# DC-DC-Converters_3.net
KiCad netlist of a schematic drawn in Altium Designer
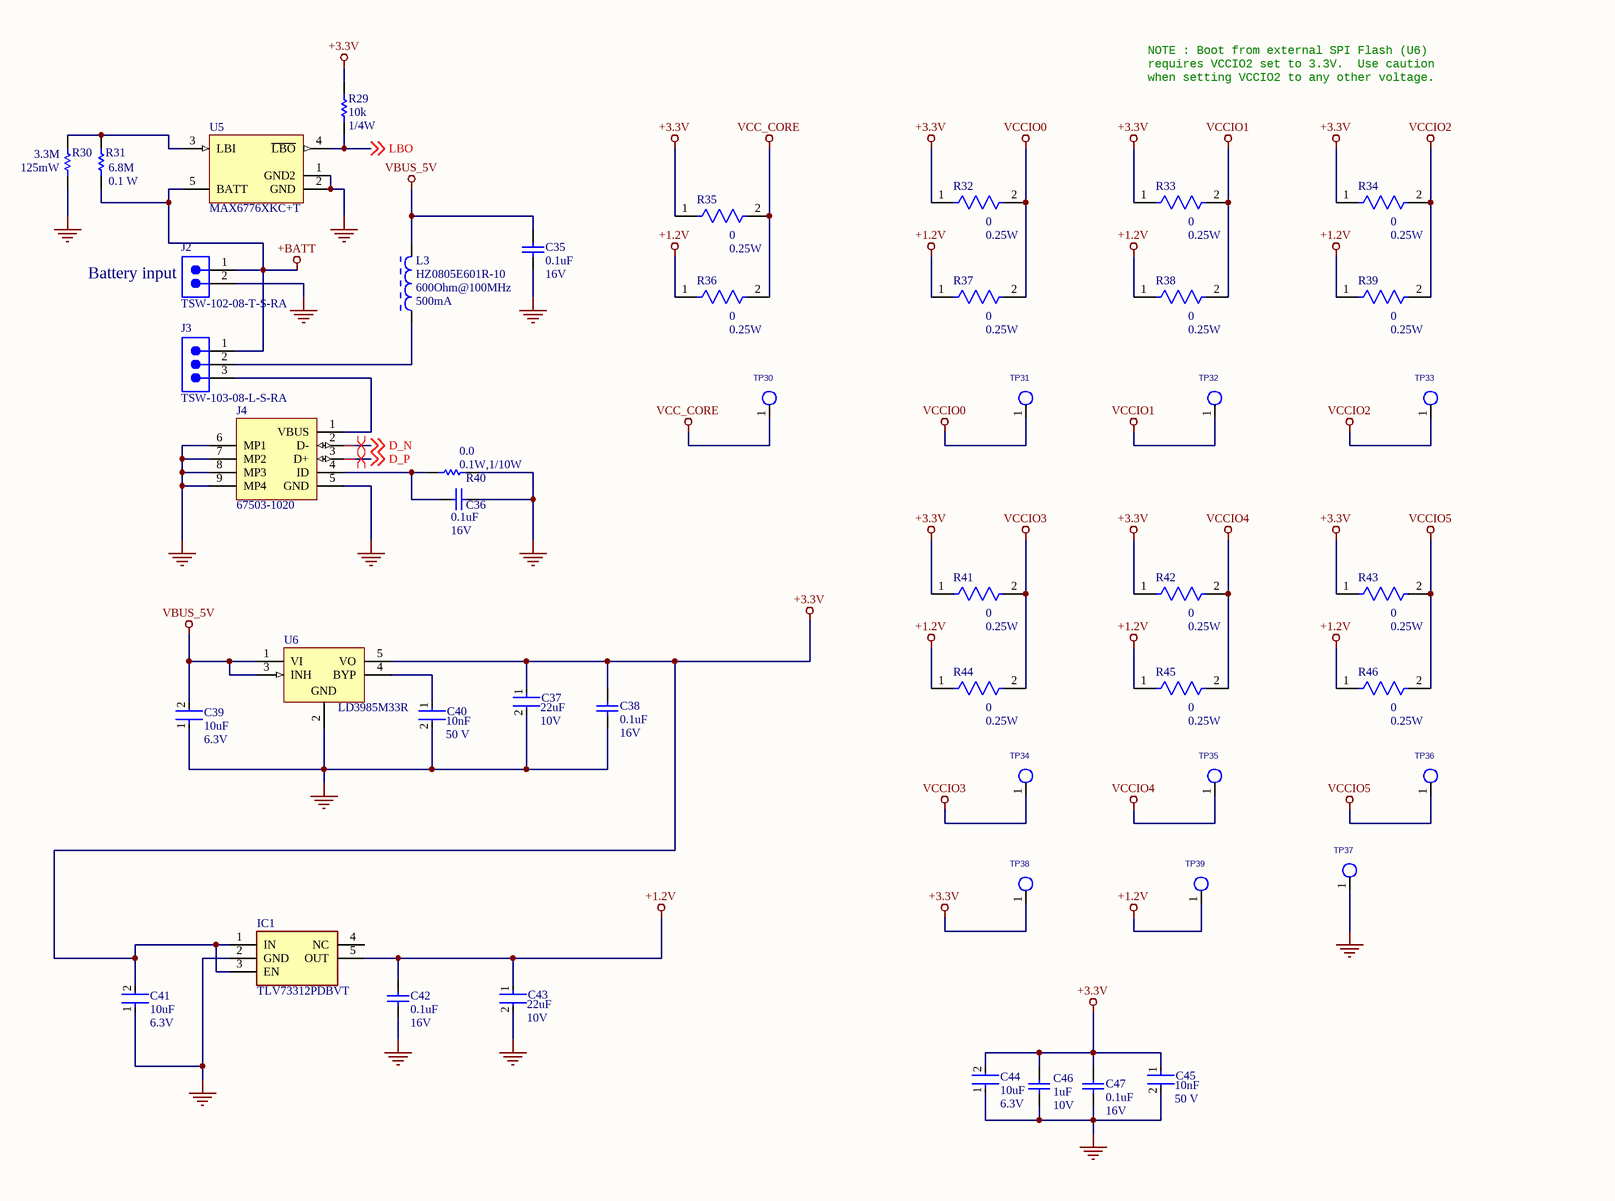
[diagram p0: DC-DC-Converters 3.SchDoc]

(export (version "E")
  (design (tool "Eeschema 10.0.6"))
  (components
    (comp (ref "C35")
      (value "0.1uF")
      (footprint "CAPC1608X87X35ML15T15")
      (description "Ceramic Capacitor 0.1uF 16V +-10% X7R0603")
      (fields
        (field (name "PART NUMBER") "C0603C104M4RACTU")
        (field (name "MANUFACTURER") "Kemet")
        (field (name "VOLTAGE") "16V")
      )
      (libsource (lib "Altium Content Vault") (part "CAP"))
    )
    (comp (ref "C36")
      (value "0.1uF")
      (footprint "CAPC1608X87X35ML15T15")
      (description "Ceramic Capacitor 0.1uF 16V +-10% X7R0603")
      (fields
        (field (name "PART NUMBER") "C0603C104M4RACTU")
        (field (name "MANUFACTURER") "Kemet")
        (field (name "VOLTAGE") "16V")
      )
      (libsource (lib "Altium Content Vault") (part "CAP"))
    )
    (comp (ref "C37")
      (value "22uF")
      (footprint "FP-GRM188-0_2-IPC_C")
      (description "Chip Multilayer Ceramic Capacitors for General Purpose, 0603, 22uF, X5R, 15%, 20%, 10V")
      (fields
        (field (name "TOLERANCE") "20%")
        (field (name "VOLTAGE") "10V")
        (field (name "PART NUMBER") "GRM188R61A226ME15D")
      )
      (libsource (lib "Altium Content Vault") (part "11868f565c42a9108669ba33697ecf6"))
    )
    (comp (ref "C38")
      (value "0.1uF")
      (footprint "CAPC1608X87X35ML15T15")
      (description "Ceramic Capacitor 0.1uF 16V +-10% X7R0603")
      (fields
        (field (name "PART NUMBER") "C0603C104M4RACTU")
        (field (name "MANUFACTURER") "Kemet")
        (field (name "VOLTAGE") "16V")
      )
      (libsource (lib "Altium Content Vault") (part "CAP"))
    )
    (comp (ref "C39")
      (value "10uF")
      (footprint "FP-CL10-IPC_C")
      (description "Cap Ceramic 10uF 6.3V X5R ±20% Pad SMD 0603 +85°C T/R")
      (fields
        (field (name "VOLTAGE") "6.3V")
        (field (name "TOLERANCE") "20%")
        (field (name "MANUFACTURER") "Samsung")
      )
      (libsource (lib "Altium Content Vault") (part "b4654b650e69147ec39a6b967a45e02"))
    )
    (comp (ref "C40")
      (value "10nF")
      (footprint "FP-C0805C-DN-MFG")
      (description "CAP CER 10000PF 50V X7R 0805")
      (fields
        (field (name "VOLTAGE") "50 V")
        (field (name "PART NUMBER") "C0805C103K5RACAUTO")
        (field (name "MANUFACTURER") "KEMET")
      )
      (libsource (lib "Altium Content Vault") (part "b4654b650e69147ec39a6b967a45e02"))
    )
    (comp (ref "C41")
      (value "10uF")
      (footprint "FP-CL10-IPC_C")
      (description "Cap Ceramic 10uF 6.3V X5R ±20% Pad SMD 0603 +85°C T/R")
      (fields
        (field (name "VOLTAGE") "6.3V")
        (field (name "TOLERANCE") "20%")
        (field (name "MANUFACTURER") "Samsung")
      )
      (libsource (lib "Altium Content Vault") (part "b4654b650e69147ec39a6b967a45e02"))
    )
    (comp (ref "C42")
      (value "0.1uF")
      (footprint "CAPC1608X87X35ML15T15")
      (description "Ceramic Capacitor 0.1uF 16V +-10% X7R0603")
      (fields
        (field (name "PART NUMBER") "C0603C104M4RACTU")
        (field (name "MANUFACTURER") "Kemet")
        (field (name "VOLTAGE") "16V")
      )
      (libsource (lib "Altium Content Vault") (part "CAP"))
    )
    (comp (ref "C43")
      (value "22uF")
      (footprint "FP-GRM188-0_2-IPC_C")
      (description "Chip Multilayer Ceramic Capacitors for General Purpose, 0603, 22uF, X5R, 15%, 20%, 10V")
      (fields
        (field (name "TOLERANCE") "20%")
        (field (name "VOLTAGE") "10V")
        (field (name "PART NUMBER") "GRM188R61A226ME15D")
      )
      (libsource (lib "Altium Content Vault") (part "11868f565c42a9108669ba33697ecf6"))
    )
    (comp (ref "C44")
      (value "10uF")
      (footprint "FP-CL10-IPC_C")
      (description "Cap Ceramic 10uF 6.3V X5R ±20% Pad SMD 0603 +85°C T/R")
      (fields
        (field (name "VOLTAGE") "6.3V")
        (field (name "TOLERANCE") "20%")
        (field (name "MANUFACTURER") "Samsung")
      )
      (libsource (lib "Altium Content Vault") (part "b4654b650e69147ec39a6b967a45e02"))
    )
    (comp (ref "C45")
      (value "10nF")
      (footprint "FP-C0805C-DN-MFG")
      (description "CAP CER 10000PF 50V X7R 0805")
      (fields
        (field (name "VOLTAGE") "50 V")
        (field (name "PART NUMBER") "C0805C103K5RACAUTO")
        (field (name "MANUFACTURER") "KEMET")
      )
      (libsource (lib "Altium Content Vault") (part "b4654b650e69147ec39a6b967a45e02"))
    )
    (comp (ref "C46")
      (value "1uF")
      (footprint "CAPC1608X90X35ML15T15")
      (fields
        (field (name "MANUFACTURER") "Kemet")
        (field (name "PART NUMBER") "C0603C105K8RACTU")
        (field (name "VOLTAGE") "10V")
      )
      (libsource (lib "Altium Content Vault") (part "CAP"))
    )
    (comp (ref "C47")
      (value "0.1uF")
      (footprint "CAPC1608X87X35ML15T15")
      (description "Ceramic Capacitor 0.1uF 16V +-10% X7R0603")
      (fields
        (field (name "PART NUMBER") "C0603C104M4RACTU")
        (field (name "MANUFACTURER") "Kemet")
        (field (name "VOLTAGE") "16V")
      )
      (libsource (lib "Altium Content Vault") (part "CAP"))
    )
    (comp (ref "IC1")
      (value "TLV73312PDBVT")
      (footprint "SamacSys:SOT95P280X145-5N")
      (description "Integrated Circuit")
      (fields (field (name "MOUSER PART NUMBER") "595-TLV73312PDBVT"))
      (libsource (lib "*") (part "TLV73312PDBVT"))
    )
    (comp (ref "J2")
      (value "TSW-102-08-T-S-RA")
      (footprint "SMTC-TSW-102-08-X-S-RA")
      (fields (field (name "MANUFACTURER") "Samtec"))
      (libsource (lib "Altium Content Vault") (part "SMTC-TSW-102-X-X-S-X"))
    )
    (comp (ref "J3")
      (value "TSW-103-08-L-S-RA")
      (footprint "SMTC-TSW-103-08-X-S-RA")
      (fields (field (name "MANUFACTURER") "Samtec"))
      (libsource (lib "Altium Content Vault") (part "SMTC-TSW-103-X-X-S-X"))
    )
    (comp (ref "J4")
      (value "67503-1020")
      (footprint "MOLX-67503-1020_V")
      (description "USB, MINI, SMD, RA KME04-USBMU03A01")
      (fields (field (name "MANUFACTURER") "Molex"))
      (libsource (lib "Altium Content Vault") (part "MOLX-67503-1020"))
    )
    (comp (ref "L3")
      (value "HZ0805E601R-10")
      (footprint "LIRD-LI0805H151R-10-2_V")
      (fields
        (field (name "IMPEDANCE @ FREQUENCY") "600Ohm@100MHz")
        (field (name "MANUFACTURER") "Laird")
        (field (name "CURRENT RATING (MAX)") "500mA")
      )
      (libsource (lib "Altium Content Vault") (part "IND-FB-2"))
    )
    (comp (ref "R29")
      (value "10k")
      (footprint "RESC3216X70X50NL05T20")
      (description "Res Thick Film 1206 10k Ohms 5% 1/4W")
      (fields
        (field (name "PART NUMBER") "ERJ-8GEYJ103V")
        (field (name "MANUFACTURER") "Panasonic")
        (field (name "POWER") "1/4W")
      )
      (libsource (lib "Altium Content Vault") (part "RES"))
    )
    (comp (ref "R30")
      (value "3.3M")
      (footprint "RESC2013X50X30LL20T20")
      (fields
        (field (name "MANUFACTURER") "Vishay Dale")
        (field (name "PART NUMBER") "CRCW08053M30FKEA")
        (field (name "POWER") "125mW")
      )
      (libsource (lib "Altium Content Vault") (part "RES"))
    )
    (comp (ref "R31")
      (value "6.8M")
      (footprint "RESC0603(1608)_L")
      (description "6M8 0.1W 5% 0603 (1608 Metric)  SMD")
      (fields
        (field (name "POWER") "0.1 W")
        (field (name "TOLERANCE") "5 %")
        (field (name "PART NUMBER") "ERJ-3GEYJ685V")
      )
      (libsource (lib "Altium Content Vault") (part "RES"))
    )
    (comp (ref "R32")
      (value "0")
      (footprint "FP-RC1206-MFG")
      (description "RES SMD 0 OHM JUMPER 1/4W 1206")
      (fields
        (field (name "PART NUMBER") "RC1206JR-070RL")
        (field (name "MANUFACTURER") "YAGEO")
        (field (name "POWER") "0.25W")
      )
      (libsource (lib "Altium Content Vault") (part "1029c3af85768c4190bb7ad29bc67b5"))
    )
    (comp (ref "R33")
      (value "0")
      (footprint "FP-RC1206-MFG")
      (description "RES SMD 0 OHM JUMPER 1/4W 1206")
      (fields
        (field (name "PART NUMBER") "RC1206JR-070RL")
        (field (name "MANUFACTURER") "YAGEO")
        (field (name "POWER") "0.25W")
      )
      (libsource (lib "Altium Content Vault") (part "1029c3af85768c4190bb7ad29bc67b5"))
    )
    (comp (ref "R34")
      (value "0")
      (footprint "FP-RC1206-MFG")
      (description "RES SMD 0 OHM JUMPER 1/4W 1206")
      (fields
        (field (name "PART NUMBER") "RC1206JR-070RL")
        (field (name "MANUFACTURER") "YAGEO")
        (field (name "POWER") "0.25W")
      )
      (libsource (lib "Altium Content Vault") (part "1029c3af85768c4190bb7ad29bc67b5"))
    )
    (comp (ref "R35")
      (value "0")
      (footprint "FP-RC1206-MFG")
      (description "RES SMD 0 OHM JUMPER 1/4W 1206")
      (fields
        (field (name "PART NUMBER") "RC1206JR-070RL")
        (field (name "MANUFACTURER") "YAGEO")
        (field (name "POWER") "0.25W")
      )
      (libsource (lib "Altium Content Vault") (part "1029c3af85768c4190bb7ad29bc67b5"))
    )
    (comp (ref "R36")
      (value "0")
      (footprint "FP-RC1206-MFG")
      (description "RES SMD 0 OHM JUMPER 1/4W 1206")
      (fields
        (field (name "PART NUMBER") "RC1206JR-070RL")
        (field (name "MANUFACTURER") "YAGEO")
        (field (name "POWER") "0.25W")
      )
      (libsource (lib "Altium Content Vault") (part "1029c3af85768c4190bb7ad29bc67b5"))
    )
    (comp (ref "R37")
      (value "0")
      (footprint "FP-RC1206-MFG")
      (description "RES SMD 0 OHM JUMPER 1/4W 1206")
      (fields
        (field (name "PART NUMBER") "RC1206JR-070RL")
        (field (name "MANUFACTURER") "YAGEO")
        (field (name "POWER") "0.25W")
      )
      (libsource (lib "Altium Content Vault") (part "1029c3af85768c4190bb7ad29bc67b5"))
    )
    (comp (ref "R38")
      (value "0")
      (footprint "FP-RC1206-MFG")
      (description "RES SMD 0 OHM JUMPER 1/4W 1206")
      (fields
        (field (name "PART NUMBER") "RC1206JR-070RL")
        (field (name "MANUFACTURER") "YAGEO")
        (field (name "POWER") "0.25W")
      )
      (libsource (lib "Altium Content Vault") (part "1029c3af85768c4190bb7ad29bc67b5"))
    )
    (comp (ref "R39")
      (value "0")
      (footprint "FP-RC1206-MFG")
      (description "RES SMD 0 OHM JUMPER 1/4W 1206")
      (fields
        (field (name "PART NUMBER") "RC1206JR-070RL")
        (field (name "MANUFACTURER") "YAGEO")
        (field (name "POWER") "0.25W")
      )
      (libsource (lib "Altium Content Vault") (part "1029c3af85768c4190bb7ad29bc67b5"))
    )
    (comp (ref "R40")
      (value "0.0")
      (footprint "RESC1608X55X35LL10T10")
      (description "Chip Resistor, 0 Ohm, +/- 5%, 0.1 W, -55 to 155 degC, 0603 (1608 Metric), RoHS, Tape and Reel")
      (fields
        (field (name "POWER") "0.1W,1/10W")
        (field (name "MANUFACTURER") "Samsung-Electro-Mechanics-America,-Inc.")
        (field (name "TOLERANCE") "Jumper")
      )
      (libsource (lib "Altium Content Vault") (part "RES-2"))
    )
    (comp (ref "R41")
      (value "0")
      (footprint "FP-RC1206-MFG")
      (description "RES SMD 0 OHM JUMPER 1/4W 1206")
      (fields
        (field (name "PART NUMBER") "RC1206JR-070RL")
        (field (name "MANUFACTURER") "YAGEO")
        (field (name "POWER") "0.25W")
      )
      (libsource (lib "Altium Content Vault") (part "1029c3af85768c4190bb7ad29bc67b5"))
    )
    (comp (ref "R42")
      (value "0")
      (footprint "FP-RC1206-MFG")
      (description "RES SMD 0 OHM JUMPER 1/4W 1206")
      (fields
        (field (name "PART NUMBER") "RC1206JR-070RL")
        (field (name "MANUFACTURER") "YAGEO")
        (field (name "POWER") "0.25W")
      )
      (libsource (lib "Altium Content Vault") (part "1029c3af85768c4190bb7ad29bc67b5"))
    )
    (comp (ref "R43")
      (value "0")
      (footprint "FP-RC1206-MFG")
      (description "RES SMD 0 OHM JUMPER 1/4W 1206")
      (fields
        (field (name "PART NUMBER") "RC1206JR-070RL")
        (field (name "MANUFACTURER") "YAGEO")
        (field (name "POWER") "0.25W")
      )
      (libsource (lib "Altium Content Vault") (part "1029c3af85768c4190bb7ad29bc67b5"))
    )
    (comp (ref "R44")
      (value "0")
      (footprint "FP-RC1206-MFG")
      (description "RES SMD 0 OHM JUMPER 1/4W 1206")
      (fields
        (field (name "PART NUMBER") "RC1206JR-070RL")
        (field (name "MANUFACTURER") "YAGEO")
        (field (name "POWER") "0.25W")
      )
      (libsource (lib "Altium Content Vault") (part "1029c3af85768c4190bb7ad29bc67b5"))
    )
    (comp (ref "R45")
      (value "0")
      (footprint "FP-RC1206-MFG")
      (description "RES SMD 0 OHM JUMPER 1/4W 1206")
      (fields
        (field (name "PART NUMBER") "RC1206JR-070RL")
        (field (name "MANUFACTURER") "YAGEO")
        (field (name "POWER") "0.25W")
      )
      (libsource (lib "Altium Content Vault") (part "1029c3af85768c4190bb7ad29bc67b5"))
    )
    (comp (ref "R46")
      (value "0")
      (footprint "FP-RC1206-MFG")
      (description "RES SMD 0 OHM JUMPER 1/4W 1206")
      (fields
        (field (name "PART NUMBER") "RC1206JR-070RL")
        (field (name "MANUFACTURER") "YAGEO")
        (field (name "POWER") "0.25W")
      )
      (libsource (lib "Altium Content Vault") (part "1029c3af85768c4190bb7ad29bc67b5"))
    )
    (comp (ref "TP30")
      (value "tp_s_40_63")
      (footprint "tp_s_40_63")
      (description "Square test point, 40mil inner diameter, 63mil outer diameter")
      (libsource (lib "*") (part "TP_S_40_63"))
    )
    (comp (ref "TP31")
      (value "tp_s_40_63")
      (footprint "tp_s_40_63")
      (description "Square test point, 40mil inner diameter, 63mil outer diameter")
      (libsource (lib "*") (part "TP_S_40_63"))
    )
    (comp (ref "TP32")
      (value "tp_s_40_63")
      (footprint "tp_s_40_63")
      (description "Square test point, 40mil inner diameter, 63mil outer diameter")
      (libsource (lib "*") (part "TP_S_40_63"))
    )
    (comp (ref "TP33")
      (value "tp_s_40_63")
      (footprint "tp_s_40_63")
      (description "Square test point, 40mil inner diameter, 63mil outer diameter")
      (libsource (lib "*") (part "TP_S_40_63"))
    )
    (comp (ref "TP34")
      (value "tp_s_40_63")
      (footprint "tp_s_40_63")
      (description "Square test point, 40mil inner diameter, 63mil outer diameter")
      (libsource (lib "*") (part "TP_S_40_63"))
    )
    (comp (ref "TP35")
      (value "tp_s_40_63")
      (footprint "tp_s_40_63")
      (description "Square test point, 40mil inner diameter, 63mil outer diameter")
      (libsource (lib "*") (part "TP_S_40_63"))
    )
    (comp (ref "TP36")
      (value "tp_s_40_63")
      (footprint "tp_s_40_63")
      (description "Square test point, 40mil inner diameter, 63mil outer diameter")
      (libsource (lib "*") (part "TP_S_40_63"))
    )
    (comp (ref "TP37")
      (value "tp_s_40_63")
      (footprint "tp_s_40_63")
      (description "Square test point, 40mil inner diameter, 63mil outer diameter")
      (libsource (lib "*") (part "TP_S_40_63"))
    )
    (comp (ref "TP38")
      (value "tp_s_40_63")
      (footprint "tp_s_40_63")
      (description "Square test point, 40mil inner diameter, 63mil outer diameter")
      (libsource (lib "*") (part "TP_S_40_63"))
    )
    (comp (ref "TP39")
      (value "tp_s_40_63")
      (footprint "tp_s_40_63")
      (description "Square test point, 40mil inner diameter, 63mil outer diameter")
      (libsource (lib "*") (part "TP_S_40_63"))
    )
    (comp (ref "U5")
      (value "MAX6776XKC+T")
      (footprint "X5+1_N")
      (libsource (lib "Altium Content Vault") (part "MAX-MAX6776-SOT5"))
    )
    (comp (ref "U6")
      (value "LD3985M33R")
      (footprint "SOT23-5L_N")
      (libsource (lib "Altium Content Vault") (part "PM-REG-LD3985-SOT5"))
    )
  )
  (nets
    (net (code "1") (name "+1.2V") (class "Default")
      (node (ref "C42") (pin "1") (pinfunction "1_1") (pintype "passive"))
      (node (ref "C43") (pin "1") (pinfunction "1_1") (pintype "passive"))
      (node (ref "IC1") (pin "5") (pinfunction "OUT_5") (pintype "passive"))
      (node (ref "R36") (pin "1") (pinfunction "1_1") (pintype "passive"))
      (node (ref "R37") (pin "1") (pinfunction "1_1") (pintype "passive"))
      (node (ref "R38") (pin "1") (pinfunction "1_1") (pintype "passive"))
      (node (ref "R39") (pin "1") (pinfunction "1_1") (pintype "passive"))
      (node (ref "R44") (pin "1") (pinfunction "1_1") (pintype "passive"))
      (node (ref "R45") (pin "1") (pinfunction "1_1") (pintype "passive"))
      (node (ref "R46") (pin "1") (pinfunction "1_1") (pintype "passive"))
      (node (ref "TP39") (pin "1") (pinfunction "TP_1") (pintype "passive"))
    )
    (net (code "2") (name "+3.3V") (class "Default")
      (node (ref "C37") (pin "1") (pinfunction "1_1") (pintype "passive"))
      (node (ref "C38") (pin "1") (pinfunction "1_1") (pintype "passive"))
      (node (ref "C41") (pin "2") (pinfunction "2_2") (pintype "passive"))
      (node (ref "C44") (pin "2") (pinfunction "2_2") (pintype "passive"))
      (node (ref "C45") (pin "1") (pinfunction "1_1") (pintype "passive"))
      (node (ref "C46") (pin "2") (pinfunction "2_2") (pintype "passive"))
      (node (ref "C47") (pin "1") (pinfunction "1_1") (pintype "passive"))
      (node (ref "IC1") (pin "1") (pinfunction "IN_1") (pintype "passive"))
      (node (ref "IC1") (pin "3") (pinfunction "EN_3") (pintype "passive"))
      (node (ref "R29") (pin "1") (pinfunction "1_1") (pintype "passive"))
      (node (ref "R32") (pin "1") (pinfunction "1_1") (pintype "passive"))
      (node (ref "R33") (pin "1") (pinfunction "1_1") (pintype "passive"))
      (node (ref "R34") (pin "1") (pinfunction "1_1") (pintype "passive"))
      (node (ref "R35") (pin "1") (pinfunction "1_1") (pintype "passive"))
      (node (ref "R41") (pin "1") (pinfunction "1_1") (pintype "passive"))
      (node (ref "R42") (pin "1") (pinfunction "1_1") (pintype "passive"))
      (node (ref "R43") (pin "1") (pinfunction "1_1") (pintype "passive"))
      (node (ref "TP38") (pin "1") (pinfunction "TP_1") (pintype "passive"))
      (node (ref "U6") (pin "5") (pinfunction "VO_5") (pintype "power_in"))
    )
    (net (code "3") (name "+BATT") (class "Default")
      (node (ref "J2") (pin "1") (pinfunction "1_1") (pintype "passive"))
      (node (ref "J3") (pin "1") (pinfunction "1_1") (pintype "passive"))
      (node (ref "R31") (pin "1") (pinfunction "1_1") (pintype "passive"))
      (node (ref "U5") (pin "5") (pinfunction "BATT_5") (pintype "power_in"))
    )
    (net (code "4") (name "D_N") (class "Default")
      (node (ref "J4") (pin "2") (pinfunction "D-_2") (pintype "bidirectional"))
    )
    (net (code "5") (name "D_P") (class "Default")
      (node (ref "J4") (pin "3") (pinfunction "D+_3") (pintype "bidirectional"))
    )
    (net (code "6") (name "GND") (class "Default")
      (node (ref "C35") (pin "2") (pinfunction "2_2") (pintype "passive"))
      (node (ref "C36") (pin "1") (pinfunction "1_1") (pintype "passive"))
      (node (ref "C37") (pin "2") (pinfunction "2_2") (pintype "passive"))
      (node (ref "C38") (pin "2") (pinfunction "2_2") (pintype "passive"))
      (node (ref "C39") (pin "1") (pinfunction "1_1") (pintype "passive"))
      (node (ref "C40") (pin "2") (pinfunction "2_2") (pintype "passive"))
      (node (ref "C41") (pin "1") (pinfunction "1_1") (pintype "passive"))
      (node (ref "C42") (pin "2") (pinfunction "2_2") (pintype "passive"))
      (node (ref "C43") (pin "2") (pinfunction "2_2") (pintype "passive"))
      (node (ref "C44") (pin "1") (pinfunction "1_1") (pintype "passive"))
      (node (ref "C45") (pin "2") (pinfunction "2_2") (pintype "passive"))
      (node (ref "C46") (pin "1") (pinfunction "1_1") (pintype "passive"))
      (node (ref "C47") (pin "2") (pinfunction "2_2") (pintype "passive"))
      (node (ref "IC1") (pin "2") (pinfunction "GND_2") (pintype "passive"))
      (node (ref "J2") (pin "2") (pinfunction "2_2") (pintype "passive"))
      (node (ref "J4") (pin "5") (pinfunction "GND_5") (pintype "power_in"))
      (node (ref "J4") (pin "6") (pinfunction "MP1_6") (pintype "passive"))
      (node (ref "J4") (pin "7") (pinfunction "MP2_7") (pintype "passive"))
      (node (ref "J4") (pin "8") (pinfunction "MP3_8") (pintype "passive"))
      (node (ref "J4") (pin "9") (pinfunction "MP4_9") (pintype "passive"))
      (node (ref "R30") (pin "1") (pinfunction "1_1") (pintype "passive"))
      (node (ref "R40") (pin "2") (pinfunction "2_2") (pintype "passive"))
      (node (ref "TP37") (pin "1") (pinfunction "TP_1") (pintype "passive"))
      (node (ref "U5") (pin "1") (pinfunction "GND2_1") (pintype "power_in"))
      (node (ref "U5") (pin "2") (pinfunction "GND_2") (pintype "power_in"))
      (node (ref "U6") (pin "2") (pinfunction "GND_2") (pintype "power_in"))
    )
    (net (code "7") (name "LBO") (class "Default")
      (node (ref "R29") (pin "2") (pinfunction "2_2") (pintype "passive"))
      (node (ref "U5") (pin "4") (pinfunction "~{LBO}_4") (pintype "output"))
    )
    (net (code "8") (name "Net-(J3-Pad2)") (class "Default")
      (node (ref "J3") (pin "2") (pinfunction "2_2") (pintype "passive"))
      (node (ref "L3") (pin "1") (pinfunction "1_1") (pintype "passive"))
    )
    (net (code "9") (name "Net-(J4-ID)") (class "Default")
      (node (ref "C36") (pin "2") (pinfunction "2_2") (pintype "passive"))
      (node (ref "J4") (pin "4") (pinfunction "ID_4") (pintype "passive"))
      (node (ref "R40") (pin "1") (pinfunction "1_1") (pintype "passive"))
    )
    (net (code "10") (name "Net-(J4-VBUS)") (class "Default")
      (node (ref "J3") (pin "3") (pinfunction "3_3") (pintype "passive"))
      (node (ref "J4") (pin "1") (pinfunction "VBUS_1") (pintype "power_in"))
    )
    (net (code "11") (name "Net-(U5-LBI)") (class "Default")
      (node (ref "R30") (pin "2") (pinfunction "2_2") (pintype "passive"))
      (node (ref "R31") (pin "2") (pinfunction "2_2") (pintype "passive"))
      (node (ref "U5") (pin "3") (pinfunction "LBI_3") (pintype "input"))
    )
    (net (code "12") (name "Net-(U6-BYP)") (class "Default")
      (node (ref "C40") (pin "1") (pinfunction "1_1") (pintype "passive"))
      (node (ref "U6") (pin "4") (pinfunction "BYP_4") (pintype "passive"))
    )
    (net (code "13") (name "VBUS_5V") (class "Default")
      (node (ref "C35") (pin "1") (pinfunction "1_1") (pintype "passive"))
      (node (ref "C39") (pin "2") (pinfunction "2_2") (pintype "passive"))
      (node (ref "L3") (pin "2") (pinfunction "2_2") (pintype "passive"))
      (node (ref "U6") (pin "1") (pinfunction "VI_1") (pintype "power_in"))
      (node (ref "U6") (pin "3") (pinfunction "INH_3") (pintype "input"))
    )
    (net (code "14") (name "VCCIO0") (class "Default")
      (node (ref "R32") (pin "2") (pinfunction "2_2") (pintype "passive"))
      (node (ref "R37") (pin "2") (pinfunction "2_2") (pintype "passive"))
      (node (ref "TP31") (pin "1") (pinfunction "TP_1") (pintype "passive"))
    )
    (net (code "15") (name "VCCIO1") (class "Default")
      (node (ref "R33") (pin "2") (pinfunction "2_2") (pintype "passive"))
      (node (ref "R38") (pin "2") (pinfunction "2_2") (pintype "passive"))
      (node (ref "TP32") (pin "1") (pinfunction "TP_1") (pintype "passive"))
    )
    (net (code "16") (name "VCCIO2") (class "Default")
      (node (ref "R34") (pin "2") (pinfunction "2_2") (pintype "passive"))
      (node (ref "R39") (pin "2") (pinfunction "2_2") (pintype "passive"))
      (node (ref "TP33") (pin "1") (pinfunction "TP_1") (pintype "passive"))
    )
    (net (code "17") (name "VCCIO3") (class "Default")
      (node (ref "R41") (pin "2") (pinfunction "2_2") (pintype "passive"))
      (node (ref "R44") (pin "2") (pinfunction "2_2") (pintype "passive"))
      (node (ref "TP34") (pin "1") (pinfunction "TP_1") (pintype "passive"))
    )
    (net (code "18") (name "VCCIO4") (class "Default")
      (node (ref "R42") (pin "2") (pinfunction "2_2") (pintype "passive"))
      (node (ref "R45") (pin "2") (pinfunction "2_2") (pintype "passive"))
      (node (ref "TP35") (pin "1") (pinfunction "TP_1") (pintype "passive"))
    )
    (net (code "19") (name "VCCIO5") (class "Default")
      (node (ref "R43") (pin "2") (pinfunction "2_2") (pintype "passive"))
      (node (ref "R46") (pin "2") (pinfunction "2_2") (pintype "passive"))
      (node (ref "TP36") (pin "1") (pinfunction "TP_1") (pintype "passive"))
    )
    (net (code "20") (name "VCC_CORE") (class "Default")
      (node (ref "R35") (pin "2") (pinfunction "2_2") (pintype "passive"))
      (node (ref "R36") (pin "2") (pinfunction "2_2") (pintype "passive"))
      (node (ref "TP30") (pin "1") (pinfunction "TP_1") (pintype "passive"))
    )
    (net (code "21") (name "unconnected-(IC1-NC-Pad4)") (class "Default")
      (node (ref "IC1") (pin "4") (pinfunction "NC_4") (pintype "passive"))
    )
  )
)
